# card.net
KiCad netlist of a schematic drawn in EAGLE
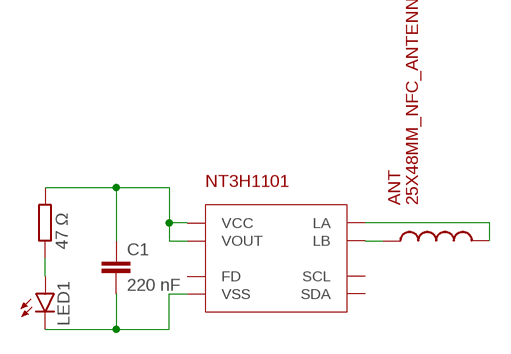
[diagram p0: schematic, sheet 1]

(export (version "E")
  (design (tool "Eeschema 10.0.6"))
  (components
    (comp (ref "ANT")
      (value "25X48MM_NFC_ANTENNA")
      (footprint "eagle-import:25X48MM_NFC_ANTENNA")
      (libsource (lib "eagle-import") (part "25X48MM_NFC_ANTENNA"))
    )
    (comp (ref "C1")
      (value "220 nF")
      (footprint "eagle-import:C0603")
      (libsource (lib "eagle-import") (part "C-EUC0603"))
    )
    (comp (ref "LED1")
      (value "LEDCHIP-LED0603")
      (footprint "eagle-import:CHIP-LED0603")
      (libsource (lib "eagle-import") (part "LEDCHIP-LED0603"))
    )
    (comp (ref "NT3H1101")
      (value "NT3H")
      (footprint "eagle-import:XQFN8")
      (libsource (lib "eagle-import") (part "NT3H"))
    )
    (comp (ref "R1")
      (value "47 Ω")
      (footprint "eagle-import:R0603")
      (libsource (lib "eagle-import") (part "R-EU_R0603"))
    )
  )
  (nets
    (net (code "1") (name "Net-(ANT-PadP$1)") (class "Default")
      (node (ref "ANT") (pin "P$1") (pinfunction "P$1_P$1") (pintype "bidirectional"))
      (node (ref "NT3H1101") (pin "LB") (pinfunction "LB_LB") (pintype "bidirectional"))
    )
    (net (code "2") (name "Net-(ANT-PadP$2)") (class "Default")
      (node (ref "ANT") (pin "P$2") (pinfunction "P$2_P$2") (pintype "bidirectional"))
      (node (ref "NT3H1101") (pin "LA") (pinfunction "LA_LA") (pintype "bidirectional"))
    )
    (net (code "3") (name "Net-(C1-Pad1)") (class "Default")
      (node (ref "C1") (pin "1") (pinfunction "1_1") (pintype "passive"))
      (node (ref "NT3H1101") (pin "VCC") (pinfunction "VCC_VCC") (pintype "bidirectional"))
      (node (ref "NT3H1101") (pin "VOUT") (pinfunction "VOUT_VOUT") (pintype "bidirectional"))
      (node (ref "R1") (pin "2") (pinfunction "2_2") (pintype "passive"))
    )
    (net (code "4") (name "Net-(C1-Pad2)") (class "Default")
      (node (ref "C1") (pin "2") (pinfunction "2_2") (pintype "passive"))
      (node (ref "LED1") (pin "C") (pinfunction "C_C") (pintype "passive"))
      (node (ref "NT3H1101") (pin "VSS") (pinfunction "VSS_VSS") (pintype "bidirectional"))
    )
    (net (code "5") (name "Net-(LED1-PadA)") (class "Default")
      (node (ref "LED1") (pin "A") (pinfunction "A_A") (pintype "passive"))
      (node (ref "R1") (pin "1") (pinfunction "1_1") (pintype "passive"))
    )
    (net (code "6") (name "unconnected-(NT3H1101-PadFD)") (class "Default")
      (node (ref "NT3H1101") (pin "FD") (pinfunction "FD_FD") (pintype "bidirectional"))
    )
    (net (code "7") (name "unconnected-(NT3H1101-PadSCL)") (class "Default")
      (node (ref "NT3H1101") (pin "SCL") (pinfunction "SCL_SCL") (pintype "bidirectional"))
    )
    (net (code "8") (name "unconnected-(NT3H1101-PadSDA)") (class "Default")
      (node (ref "NT3H1101") (pin "SDA") (pinfunction "SDA_SDA") (pintype "bidirectional"))
    )
  )
)
